# ProPrj_TweenWave_2025-11-29.net
KiCad netlist of a schematic drawn in EasyEDA Pro
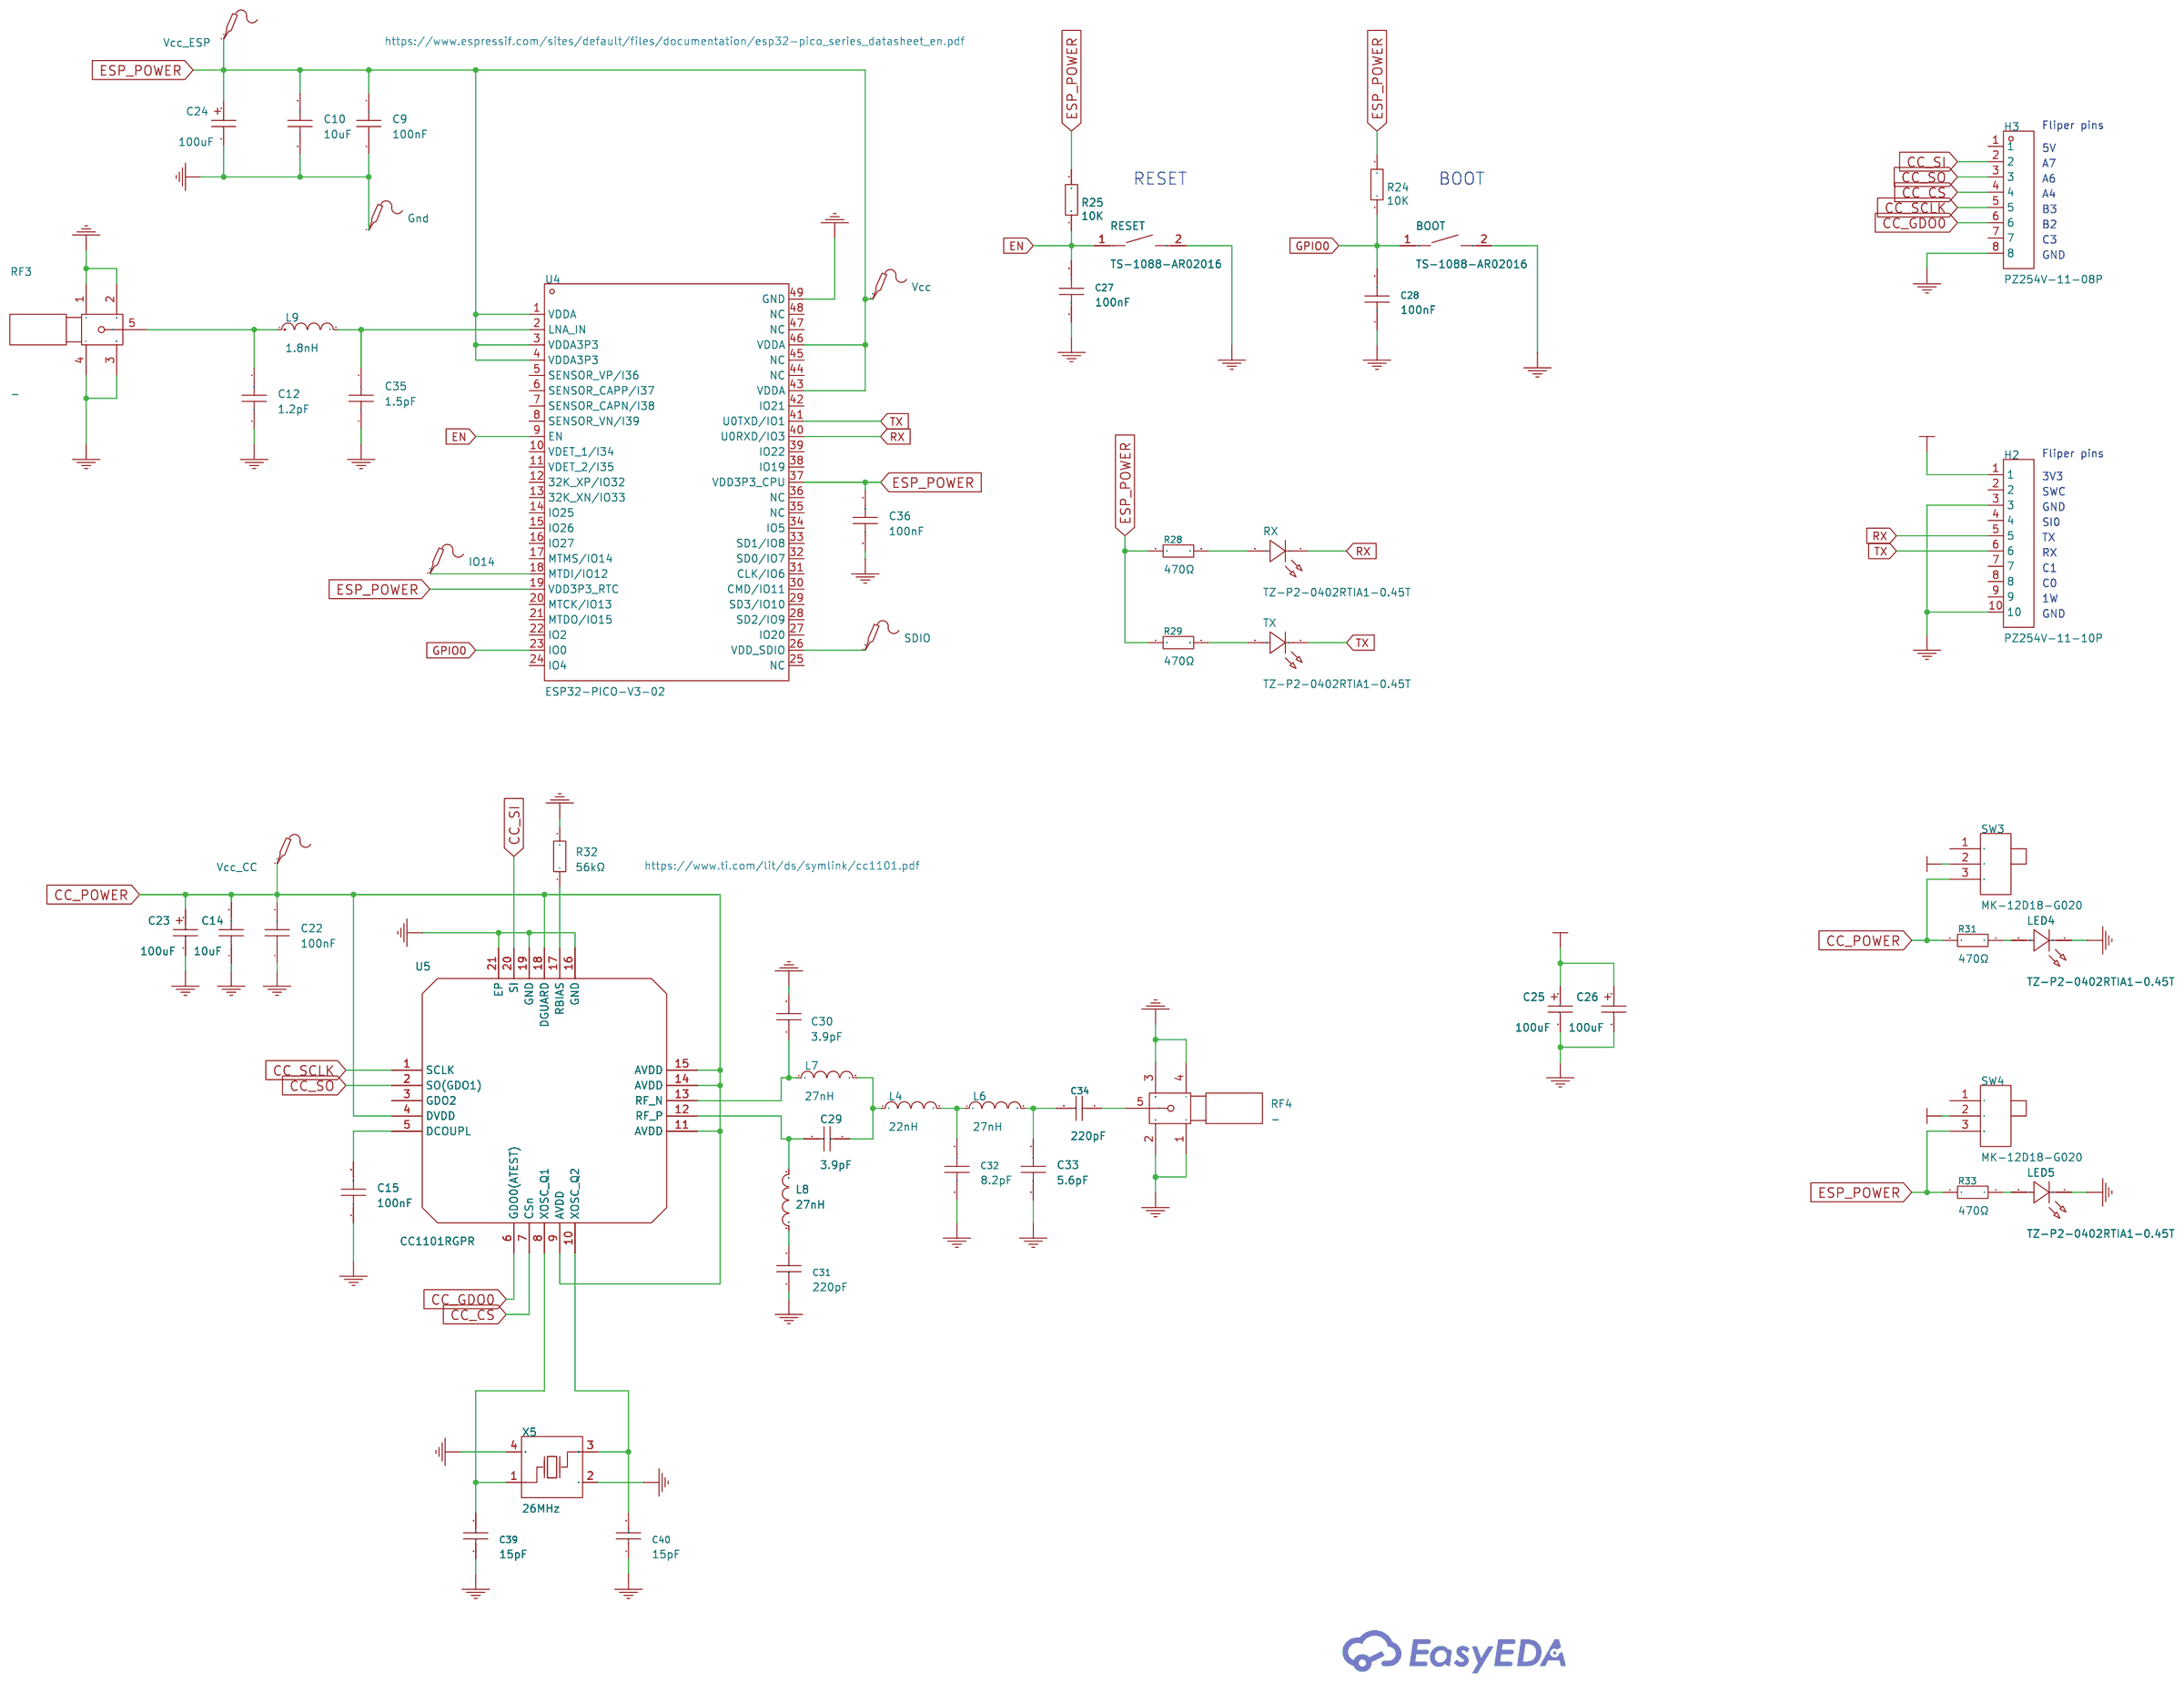
[diagram p0: schematic sheet]

(export (version "E")
  (design (tool "Eeschema 10.0.6"))
  (components
    (comp (ref "BOOT")
      (value "TS-1088-AR02016")
      (footprint "easyedapro:SW-SMD_L3.9-W3.0-P4.45")
      (fields (field (name "Manufacturer") "XUNPU(讯普)"))
      (libsource (lib "easyedapro") (part "TS-1088-AR02016"))
    )
    (comp (ref "C9")
      (value "100nF")
      (footprint "easyedapro:C0603")
      (description "Capacitance:100nF Tolerance:±10% Tolerance:±10% Voltage Rating:50V Temperature Coefficient:X7R")
      (fields
        (field (name "Manufacturer Part") "CC0603KRX7R9BB104")
        (field (name "Manufacturer") "YAGEO(国巨)")
      )
      (libsource (lib "easyedapro") (part "CC0603KRX7R9BB104"))
    )
    (comp (ref "C10")
      (value "10uF")
      (footprint "easyedapro:C0603")
      (fields
        (field (name "Manufacturer Part") "CL10A106MP8NNNC")
        (field (name "Manufacturer") "SAMSUNG(三星)")
      )
      (libsource (lib "easyedapro") (part "CL10A106MP8NNNC"))
    )
    (comp (ref "C12")
      (value "1.2pF")
      (footprint "easyedapro:C0201")
      (fields
        (field (name "Manufacturer Part") "GRM0335C1H1R2BA01D")
        (field (name "Manufacturer") "muRata(村田)")
      )
      (libsource (lib "easyedapro") (part "GRM0335C1H1R2BA01D"))
    )
    (comp (ref "C14")
      (value "10uF")
      (footprint "easyedapro:C0603")
      (fields
        (field (name "Manufacturer Part") "CL10A106MP8NNNC")
        (field (name "Manufacturer") "SAMSUNG(三星)")
      )
      (libsource (lib "easyedapro") (part "CL10A106MP8NNNC"))
    )
    (comp (ref "C15")
      (value "100nF")
      (footprint "easyedapro:C0603")
      (description "Capacitance:100nF Tolerance:±10% Tolerance:±10% Voltage Rating:50V Temperature Coefficient:X7R")
      (fields
        (field (name "Manufacturer Part") "CC0603KRX7R9BB104")
        (field (name "Manufacturer") "YAGEO(国巨)")
      )
      (libsource (lib "easyedapro") (part "CC0603KRX7R9BB104"))
    )
    (comp (ref "C22")
      (value "100nF")
      (footprint "easyedapro:C0603")
      (description "Capacitance:100nF Tolerance:±10% Tolerance:±10% Voltage Rating:50V Temperature Coefficient:X7R")
      (fields
        (field (name "Manufacturer Part") "CC0603KRX7R9BB104")
        (field (name "Manufacturer") "YAGEO(国巨)")
      )
      (libsource (lib "easyedapro") (part "CC0603KRX7R9BB104"))
    )
    (comp (ref "C23")
      (value "100uF")
      (footprint "easyedapro:CASE-B_3528")
      (fields (field (name "Manufacturer Part") "TAJB107K006RNJ") (field (name "Manufacturer") "Kyocera AVX"))
      (libsource (lib "easyedapro") (part "TAJB107K006RNJ"))
    )
    (comp (ref "C24")
      (value "100uF")
      (footprint "easyedapro:CASE-B_3528")
      (fields (field (name "Manufacturer Part") "TAJB107K006RNJ") (field (name "Manufacturer") "Kyocera AVX"))
      (libsource (lib "easyedapro") (part "TAJB107K006RNJ"))
    )
    (comp (ref "C25")
      (value "100uF")
      (footprint "easyedapro:CASE-B_3528")
      (fields (field (name "Manufacturer Part") "TAJB107K006RNJ") (field (name "Manufacturer") "Kyocera AVX"))
      (libsource (lib "easyedapro") (part "TAJB107K006RNJ"))
    )
    (comp (ref "C26")
      (value "100uF")
      (footprint "easyedapro:CASE-B_3528")
      (fields (field (name "Manufacturer Part") "TAJB107K006RNJ") (field (name "Manufacturer") "Kyocera AVX"))
      (libsource (lib "easyedapro") (part "TAJB107K006RNJ"))
    )
    (comp (ref "C27")
      (value "100nF")
      (footprint "easyedapro:C0402")
      (fields
        (field (name "Manufacturer Part") "CC0402KRX7R7BB104")
        (field (name "Manufacturer") "YAGEO(国巨)")
      )
      (libsource (lib "easyedapro") (part "CC0402KRX7R7BB104"))
    )
    (comp (ref "C28")
      (value "100nF")
      (footprint "easyedapro:C0402")
      (fields
        (field (name "Manufacturer Part") "CC0402KRX7R7BB104")
        (field (name "Manufacturer") "YAGEO(国巨)")
      )
      (libsource (lib "easyedapro") (part "CC0402KRX7R7BB104"))
    )
    (comp (ref "C29")
      (value "3.9pF")
      (footprint "easyedapro:C0402")
      (fields (field (name "Manufacturer Part") "0402CG3R9C500NT") (field (name "Manufacturer") "FH(风华)"))
      (libsource (lib "easyedapro") (part "0402CG3R9C500NT"))
    )
    (comp (ref "C30")
      (value "3.9pF")
      (footprint "easyedapro:C0402")
      (fields (field (name "Manufacturer Part") "0402CG3R9C500NT") (field (name "Manufacturer") "FH(风华)"))
      (libsource (lib "easyedapro") (part "0402CG3R9C500NT"))
    )
    (comp (ref "C31")
      (value "220pF")
      (footprint "easyedapro:C0402")
      (description "Capacitance:220pF Tolerance:±5% Tolerance:±5% Voltage Rating:50V Temperature Coefficient:NP0")
      (fields
        (field (name "Manufacturer Part") "CC0402JRNPO9BN221")
        (field (name "Manufacturer") "YAGEO(国巨)")
      )
      (libsource (lib "easyedapro") (part "CC0402JRNPO9BN221"))
    )
    (comp (ref "C32")
      (value "8.2pF")
      (footprint "easyedapro:C0402")
      (fields
        (field (name "Manufacturer Part") "CC0402BRNPO9BN8R2")
        (field (name "Manufacturer") "YAGEO(国巨)")
      )
      (libsource (lib "easyedapro") (part "CC0402BRNPO9BN8R2"))
    )
    (comp (ref "C33")
      (value "5.6pF")
      (footprint "easyedapro:C0402")
      (fields
        (field (name "Manufacturer Part") "CC0402BRNPO9BN5R6")
        (field (name "Manufacturer") "YAGEO(国巨)")
      )
      (libsource (lib "easyedapro") (part "CC0402BRNPO9BN5R6"))
    )
    (comp (ref "C34")
      (value "220pF")
      (footprint "easyedapro:C0402")
      (description "Capacitance:220pF Tolerance:±5% Tolerance:±5% Voltage Rating:50V Temperature Coefficient:NP0")
      (fields
        (field (name "Manufacturer Part") "CC0402JRNPO9BN221")
        (field (name "Manufacturer") "YAGEO(国巨)")
      )
      (libsource (lib "easyedapro") (part "CC0402JRNPO9BN221"))
    )
    (comp (ref "C35")
      (value "1.5pF")
      (footprint "easyedapro:C0201")
      (fields
        (field (name "Manufacturer Part") "GRM0335C1H1R5BA01D")
        (field (name "Manufacturer") "muRata(村田)")
      )
      (libsource (lib "easyedapro") (part "GRM0335C1H1R5BA01D"))
    )
    (comp (ref "C36")
      (value "100nF")
      (footprint "easyedapro:C0603")
      (description "Capacitance:100nF Tolerance:±10% Tolerance:±10% Voltage Rating:50V Temperature Coefficient:X7R")
      (fields
        (field (name "Manufacturer Part") "CC0603KRX7R9BB104")
        (field (name "Manufacturer") "YAGEO(国巨)")
      )
      (libsource (lib "easyedapro") (part "CC0603KRX7R9BB104"))
    )
    (comp (ref "C39")
      (value "15pF")
      (footprint "easyedapro:C0402")
      (fields
        (field (name "Manufacturer Part") "CC0402JRNPO9BN150")
        (field (name "Manufacturer") "YAGEO(国巨)")
      )
      (libsource (lib "easyedapro") (part "CC0402JRNPO9BN150"))
    )
    (comp (ref "C40")
      (value "15pF")
      (footprint "easyedapro:C0402")
      (fields
        (field (name "Manufacturer Part") "CC0402JRNPO9BN150")
        (field (name "Manufacturer") "YAGEO(国巨)")
      )
      (libsource (lib "easyedapro") (part "CC0402JRNPO9BN150"))
    )
    (comp (ref "Gnd")
      (value "~")
      (footprint "easyedapro:Test-Point-0.5mm")
      (description "Test Point 测试点")
      (libsource (lib "easyedapro") (part "Test-Point"))
    )
    (comp (ref "H2")
      (value "PZ254V-11-10P")
      (footprint "easyedapro:HDR-TH_10P-P2.54-V-M")
      (fields (field (name "Manufacturer") "XFCN(兴飞)"))
      (libsource (lib "easyedapro") (part "PZ254V-11-10P"))
    )
    (comp (ref "H3")
      (value "PZ254V-11-08P")
      (footprint "easyedapro:HDR-TH_8P-P2.54-V-M")
      (fields (field (name "Manufacturer") "XFCN(兴飞)"))
      (libsource (lib "easyedapro") (part "PZ254V-11-08P"))
    )
    (comp (ref "IO14")
      (value "~")
      (footprint "easyedapro:Test-Point-0.5mm")
      (description "Test Point 测试点")
      (libsource (lib "easyedapro") (part "Test-Point"))
    )
    (comp (ref "L4")
      (value "22nH")
      (footprint "easyedapro:L0402")
      (fields (field (name "Manufacturer Part") "LQG15HS22NJ02D") (field (name "Manufacturer") "muRata(村田)"))
      (libsource (lib "easyedapro") (part "LQG15HS22NJ02D"))
    )
    (comp (ref "L6")
      (value "27nH")
      (footprint "easyedapro:L0402-RD")
      (fields (field (name "Manufacturer Part") "LQG15HS27NJ02D") (field (name "Manufacturer") "muRata(村田)"))
      (libsource (lib "easyedapro") (part "LQG15HS27NJ02D"))
    )
    (comp (ref "L7")
      (value "27nH")
      (footprint "easyedapro:L0402-RD")
      (fields (field (name "Manufacturer Part") "LQG15HS27NJ02D") (field (name "Manufacturer") "muRata(村田)"))
      (libsource (lib "easyedapro") (part "LQG15HS27NJ02D"))
    )
    (comp (ref "L8")
      (value "27nH")
      (footprint "easyedapro:L0402-RD")
      (fields (field (name "Manufacturer Part") "LQG15HS27NJ02D") (field (name "Manufacturer") "muRata(村田)"))
      (libsource (lib "easyedapro") (part "LQG15HS27NJ02D"))
    )
    (comp (ref "L9")
      (value "1.8nH")
      (footprint "easyedapro:L0201-RD")
      (fields (field (name "Manufacturer Part") "LQP03TN1N8B02D") (field (name "Manufacturer") "muRata(村田)"))
      (libsource (lib "easyedapro") (part "LQP03TN1N8B02D"))
    )
    (comp (ref "LED4")
      (value "TZ-P2-0402RTIA1-0.45T")
      (footprint "easyedapro:LED0402-RD_RED")
      (fields (field (name "Manufacturer") "TUOZHAN(拓展光电)"))
      (libsource (lib "easyedapro") (part "TZ-P2-0402RTIA1-0.45T"))
    )
    (comp (ref "LED5")
      (value "TZ-P2-0402RTIA1-0.45T")
      (footprint "easyedapro:LED0402-RD_RED")
      (fields (field (name "Manufacturer") "TUOZHAN(拓展光电)"))
      (libsource (lib "easyedapro") (part "TZ-P2-0402RTIA1-0.45T"))
    )
    (comp (ref "R24")
      (value "10K")
      (footprint "easyedapro:R0603")
      (fields (field (name "Manufacturer Part") "RC0603DR-0710KL") (field (name "Manufacturer") "YAGEO(国巨)"))
      (libsource (lib "easyedapro") (part "10K"))
    )
    (comp (ref "R25")
      (value "10K")
      (footprint "easyedapro:R0603")
      (fields (field (name "Manufacturer Part") "RC0603DR-0710KL") (field (name "Manufacturer") "YAGEO(国巨)"))
      (libsource (lib "easyedapro") (part "10K"))
    )
    (comp (ref "R28")
      (value "470Ω")
      (footprint "easyedapro:R0402")
      (fields
        (field (name "Manufacturer Part") "0402WGF4700TCE")
        (field (name "Manufacturer") "UNI-ROYAL(厚声)")
      )
      (libsource (lib "easyedapro") (part "0402WGF4700TCE"))
    )
    (comp (ref "R29")
      (value "470Ω")
      (footprint "easyedapro:R0402")
      (fields
        (field (name "Manufacturer Part") "0402WGF4700TCE")
        (field (name "Manufacturer") "UNI-ROYAL(厚声)")
      )
      (libsource (lib "easyedapro") (part "0402WGF4700TCE"))
    )
    (comp (ref "R31")
      (value "470Ω")
      (footprint "easyedapro:R0402")
      (fields
        (field (name "Manufacturer Part") "0402WGF4700TCE")
        (field (name "Manufacturer") "UNI-ROYAL(厚声)")
      )
      (libsource (lib "easyedapro") (part "0402WGF4700TCE"))
    )
    (comp (ref "R32")
      (value "56kΩ")
      (footprint "easyedapro:R0402")
      (fields
        (field (name "Manufacturer Part") "0402WGF5602TCE")
        (field (name "Manufacturer") "UNI-ROYAL(厚声)")
      )
      (libsource (lib "easyedapro") (part "0402WGF5602TCE"))
    )
    (comp (ref "R33")
      (value "470Ω")
      (footprint "easyedapro:R0402")
      (fields
        (field (name "Manufacturer Part") "0402WGF4700TCE")
        (field (name "Manufacturer") "UNI-ROYAL(厚声)")
      )
      (libsource (lib "easyedapro") (part "0402WGF4700TCE"))
    )
    (comp (ref "RESET")
      (value "TS-1088-AR02016")
      (footprint "easyedapro:SW-SMD_L3.9-W3.0-P4.45")
      (fields (field (name "Manufacturer") "XUNPU(讯普)"))
      (libsource (lib "easyedapro") (part "TS-1088-AR02016"))
    )
    (comp (ref "RF3")
      (value "-")
      (footprint "easyedapro:SMA-SMD_BWSMA-KE-P001")
      (fields
        (field (name "Manufacturer Part") "BWSMA-KE-P001")
        (field (name "Manufacturer") "BAT WIRELESS(蝙蝠无线)")
      )
      (libsource (lib "easyedapro") (part "BWSMA-KE-P001"))
    )
    (comp (ref "RF4")
      (value "-")
      (footprint "easyedapro:SMA-SMD_BWSMA-KE-P001")
      (fields
        (field (name "Manufacturer Part") "BWSMA-KE-P001")
        (field (name "Manufacturer") "BAT WIRELESS(蝙蝠无线)")
      )
      (libsource (lib "easyedapro") (part "BWSMA-KE-P001"))
    )
    (comp (ref "RX")
      (value "TZ-P2-0402RTIA1-0.45T")
      (footprint "easyedapro:LED0402-RD_RED")
      (fields (field (name "Manufacturer") "TUOZHAN(拓展光电)"))
      (libsource (lib "easyedapro") (part "TZ-P2-0402RTIA1-0.45T"))
    )
    (comp (ref "SDIO")
      (value "~")
      (footprint "easyedapro:Test-Point-0.5mm")
      (description "Test Point 测试点")
      (libsource (lib "easyedapro") (part "Test-Point"))
    )
    (comp (ref "SW3")
      (value "MK-12D18-G020")
      (footprint "easyedapro:SW-TH_MK-12D18-G040")
      (fields (field (name "Manufacturer") "G-Switch(品赞)"))
      (libsource (lib "easyedapro") (part "MK-12D18-G020"))
    )
    (comp (ref "SW4")
      (value "MK-12D18-G020")
      (footprint "easyedapro:SW-TH_MK-12D18-G040")
      (fields (field (name "Manufacturer") "G-Switch(品赞)"))
      (libsource (lib "easyedapro") (part "MK-12D18-G020"))
    )
    (comp (ref "TX")
      (value "TZ-P2-0402RTIA1-0.45T")
      (footprint "easyedapro:LED0402-RD_RED")
      (fields (field (name "Manufacturer") "TUOZHAN(拓展光电)"))
      (libsource (lib "easyedapro") (part "TZ-P2-0402RTIA1-0.45T"))
    )
    (comp (ref "U4")
      (value "ESP32-PICO-V3-02")
      (footprint "easyedapro:QFN-48_L7.0-W7.0-P0.50-BL-EP5.1")
      (fields (field (name "Manufacturer") "ESPRESSIF(乐鑫)"))
      (libsource (lib "easyedapro") (part "ESP32-PICO-V3-02"))
    )
    (comp (ref "U5")
      (value "CC1101RGPR")
      (footprint "easyedapro:QFN-20_L4.0-W4.0-P0.5-TL-EP")
      (fields (field (name "Manufacturer") "TI(德州仪器)"))
      (libsource (lib "easyedapro") (part "CC1101RGPR"))
    )
    (comp (ref "Vcc")
      (value "~")
      (footprint "easyedapro:Test-Point-0.5mm")
      (description "Test Point 测试点")
      (libsource (lib "easyedapro") (part "Test-Point"))
    )
    (comp (ref "Vcc_CC")
      (value "~")
      (footprint "easyedapro:Test-Point-0.5mm")
      (description "Test Point 测试点")
      (libsource (lib "easyedapro") (part "Test-Point"))
    )
    (comp (ref "Vcc_ESP")
      (value "~")
      (footprint "easyedapro:Test-Point-0.5mm")
      (description "Test Point 测试点")
      (libsource (lib "easyedapro") (part "Test-Point"))
    )
    (comp (ref "X5")
      (value "26MHz")
      (footprint "easyedapro:CRYSTAL-SMD_4P-L3.2-W2.5-BL")
      (fields (field (name "Manufacturer Part") "X322526MMB4SI") (field (name "Manufacturer") "YXC(扬兴晶振)"))
      (libsource (lib "easyedapro") (part "X322526MMB4SI"))
    )
  )
  (nets
    (net (code "1") (name "3V3") (class "Default")
      (node (ref "C25") (pin "1") (pinfunction "1_1") (pintype "input"))
      (node (ref "C26") (pin "1") (pinfunction "1_1") (pintype "input"))
      (node (ref "H2") (pin "1") (pinfunction "1_1") (pintype "unspecified"))
      (node (ref "SW3") (pin "2") (pinfunction "2_2") (pintype "unspecified"))
      (node (ref "SW4") (pin "2") (pinfunction "2_2") (pintype "unspecified"))
    )
    (net (code "2") (name "CC_CS") (class "Default")
      (node (ref "H3") (pin "4") (pinfunction "4_4") (pintype "unspecified"))
      (node (ref "U5") (pin "7") (pinfunction "CSn_7") (pintype "unspecified"))
    )
    (net (code "3") (name "CC_GDO0") (class "Default")
      (node (ref "H3") (pin "6") (pinfunction "6_6") (pintype "unspecified"))
      (node (ref "U5") (pin "6") (pinfunction "GDO0(ATEST)_6") (pintype "unspecified"))
    )
    (net (code "4") (name "CC_POWER") (class "Default")
      (node (ref "C14") (pin "2") (pinfunction "2_2") (pintype "unspecified"))
      (node (ref "C22") (pin "2") (pinfunction "2_2") (pintype "unspecified"))
      (node (ref "C23") (pin "1") (pinfunction "1_1") (pintype "input"))
      (node (ref "R31") (pin "1") (pinfunction "1_1") (pintype "input"))
      (node (ref "SW3") (pin "3") (pinfunction "3_3") (pintype "unspecified"))
      (node (ref "U5") (pin "11") (pinfunction "AVDD_11") (pintype "unspecified"))
      (node (ref "U5") (pin "14") (pinfunction "AVDD_14") (pintype "unspecified"))
      (node (ref "U5") (pin "15") (pinfunction "AVDD_15") (pintype "unspecified"))
      (node (ref "U5") (pin "18") (pinfunction "DGUARD_18") (pintype "unspecified"))
      (node (ref "U5") (pin "4") (pinfunction "DVDD_4") (pintype "unspecified"))
      (node (ref "U5") (pin "9") (pinfunction "AVDD_9") (pintype "unspecified"))
      (node (ref "Vcc_CC") (pin "1") (pinfunction "1_1") (pintype "unspecified"))
    )
    (net (code "5") (name "CC_SCLK") (class "Default")
      (node (ref "H3") (pin "5") (pinfunction "5_5") (pintype "unspecified"))
      (node (ref "U5") (pin "1") (pinfunction "SCLK_1") (pintype "unspecified"))
    )
    (net (code "6") (name "CC_SI") (class "Default")
      (node (ref "H3") (pin "2") (pinfunction "2_2") (pintype "unspecified"))
      (node (ref "U5") (pin "20") (pinfunction "SI_20") (pintype "unspecified"))
    )
    (net (code "7") (name "CC_SO") (class "Default")
      (node (ref "H3") (pin "3") (pinfunction "3_3") (pintype "unspecified"))
      (node (ref "U5") (pin "2") (pinfunction "SO(GDO1)_2") (pintype "unspecified"))
    )
    (net (code "8") (name "EN") (class "Default")
      (node (ref "C27") (pin "2") (pinfunction "2_2") (pintype "input"))
      (node (ref "R25") (pin "1") (pinfunction "1_1") (pintype "input"))
      (node (ref "RESET") (pin "1") (pinfunction "1_1") (pintype "unspecified"))
      (node (ref "U4") (pin "9") (pinfunction "EN_9") (pintype "unspecified"))
    )
    (net (code "9") (name "ESP_POWER") (class "Default")
      (node (ref "C10") (pin "2") (pinfunction "2_2") (pintype "unspecified"))
      (node (ref "C24") (pin "1") (pinfunction "1_1") (pintype "input"))
      (node (ref "C36") (pin "2") (pinfunction "2_2") (pintype "unspecified"))
      (node (ref "C9") (pin "2") (pinfunction "2_2") (pintype "unspecified"))
      (node (ref "R24") (pin "2") (pinfunction "2_2") (pintype "input"))
      (node (ref "R25") (pin "2") (pinfunction "2_2") (pintype "input"))
      (node (ref "R28") (pin "1") (pinfunction "1_1") (pintype "input"))
      (node (ref "R29") (pin "1") (pinfunction "1_1") (pintype "input"))
      (node (ref "R33") (pin "1") (pinfunction "1_1") (pintype "input"))
      (node (ref "SW4") (pin "3") (pinfunction "3_3") (pintype "unspecified"))
      (node (ref "U4") (pin "1") (pinfunction "VDDA_1") (pintype "unspecified"))
      (node (ref "U4") (pin "19") (pinfunction "VDD3P3_RTC_19") (pintype "unspecified"))
      (node (ref "U4") (pin "3") (pinfunction "VDDA3P3_3") (pintype "unspecified"))
      (node (ref "U4") (pin "37") (pinfunction "VDD3P3_CPU_37") (pintype "unspecified"))
      (node (ref "U4") (pin "4") (pinfunction "VDDA3P3_4") (pintype "unspecified"))
      (node (ref "U4") (pin "43") (pinfunction "VDDA_43") (pintype "unspecified"))
      (node (ref "U4") (pin "46") (pinfunction "VDDA_46") (pintype "unspecified"))
      (node (ref "Vcc") (pin "1") (pinfunction "1_1") (pintype "unspecified"))
      (node (ref "Vcc_ESP") (pin "1") (pinfunction "1_1") (pintype "unspecified"))
    )
    (net (code "10") (name "GND") (class "Default")
      (node (ref "BOOT") (pin "2") (pinfunction "2_2") (pintype "unspecified"))
      (node (ref "C10") (pin "1") (pinfunction "1_1") (pintype "unspecified"))
      (node (ref "C12") (pin "1") (pinfunction "1_1") (pintype "unspecified"))
      (node (ref "C14") (pin "1") (pinfunction "1_1") (pintype "unspecified"))
      (node (ref "C15") (pin "1") (pinfunction "1_1") (pintype "unspecified"))
      (node (ref "C22") (pin "1") (pinfunction "1_1") (pintype "unspecified"))
      (node (ref "C23") (pin "2") (pinfunction "2_2") (pintype "input"))
      (node (ref "C24") (pin "2") (pinfunction "2_2") (pintype "input"))
      (node (ref "C25") (pin "2") (pinfunction "2_2") (pintype "input"))
      (node (ref "C26") (pin "2") (pinfunction "2_2") (pintype "input"))
      (node (ref "C27") (pin "1") (pinfunction "1_1") (pintype "input"))
      (node (ref "C28") (pin "1") (pinfunction "1_1") (pintype "input"))
      (node (ref "C30") (pin "2") (pinfunction "2_2") (pintype "input"))
      (node (ref "C31") (pin "1") (pinfunction "1_1") (pintype "input"))
      (node (ref "C32") (pin "2") (pinfunction "2_2") (pintype "input"))
      (node (ref "C33") (pin "1") (pinfunction "1_1") (pintype "unspecified"))
      (node (ref "C35") (pin "1") (pinfunction "1_1") (pintype "unspecified"))
      (node (ref "C36") (pin "1") (pinfunction "1_1") (pintype "unspecified"))
      (node (ref "C39") (pin "1") (pinfunction "1_1") (pintype "input"))
      (node (ref "C40") (pin "1") (pinfunction "1_1") (pintype "input"))
      (node (ref "C9") (pin "1") (pinfunction "1_1") (pintype "unspecified"))
      (node (ref "Gnd") (pin "1") (pinfunction "1_1") (pintype "unspecified"))
      (node (ref "H2") (pin "10") (pinfunction "10_10") (pintype "unspecified"))
      (node (ref "H2") (pin "3") (pinfunction "3_3") (pintype "unspecified"))
      (node (ref "H3") (pin "8") (pinfunction "8_8") (pintype "unspecified"))
      (node (ref "LED4") (pin "1") (pinfunction "K_1") (pintype "unspecified"))
      (node (ref "LED5") (pin "1") (pinfunction "K_1") (pintype "unspecified"))
      (node (ref "R32") (pin "2") (pinfunction "2_2") (pintype "input"))
      (node (ref "RESET") (pin "2") (pinfunction "2_2") (pintype "unspecified"))
      (node (ref "RF3") (pin "1") (pinfunction "1_1") (pintype "unspecified"))
      (node (ref "RF3") (pin "2") (pinfunction "2_2") (pintype "unspecified"))
      (node (ref "RF3") (pin "3") (pinfunction "3_3") (pintype "unspecified"))
      (node (ref "RF3") (pin "4") (pinfunction "4_4") (pintype "unspecified"))
      (node (ref "RF4") (pin "1") (pinfunction "1_1") (pintype "unspecified"))
      (node (ref "RF4") (pin "2") (pinfunction "2_2") (pintype "unspecified"))
      (node (ref "RF4") (pin "3") (pinfunction "3_3") (pintype "unspecified"))
      (node (ref "RF4") (pin "4") (pinfunction "4_4") (pintype "unspecified"))
      (node (ref "U4") (pin "49") (pinfunction "GND_49") (pintype "unspecified"))
      (node (ref "U5") (pin "16") (pinfunction "GND_16") (pintype "unspecified"))
      (node (ref "U5") (pin "19") (pinfunction "GND_19") (pintype "unspecified"))
      (node (ref "U5") (pin "21") (pinfunction "EP_21") (pintype "unspecified"))
      (node (ref "X5") (pin "2") (pinfunction "GND_2") (pintype "unspecified"))
      (node (ref "X5") (pin "4") (pinfunction "GND_4") (pintype "unspecified"))
    )
    (net (code "11") (name "GPIO0") (class "Default")
      (node (ref "BOOT") (pin "1") (pinfunction "1_1") (pintype "unspecified"))
      (node (ref "C28") (pin "2") (pinfunction "2_2") (pintype "input"))
      (node (ref "R24") (pin "1") (pinfunction "1_1") (pintype "input"))
      (node (ref "U4") (pin "23") (pinfunction "IO0_23") (pintype "unspecified"))
    )
    (net (code "12") (name "Net-(C12-Pad2)") (class "Default")
      (node (ref "C12") (pin "2") (pinfunction "2_2") (pintype "unspecified"))
      (node (ref "L9") (pin "1") (pinfunction "1_1") (pintype "input"))
      (node (ref "RF3") (pin "5") (pinfunction "5_5") (pintype "unspecified"))
    )
    (net (code "13") (name "Net-(C29-Pad2)") (class "Default")
      (node (ref "C29") (pin "2") (pinfunction "2_2") (pintype "input"))
      (node (ref "L4") (pin "1") (pinfunction "1_1") (pintype "unspecified"))
      (node (ref "L7") (pin "2") (pinfunction "2_2") (pintype "unspecified"))
    )
    (net (code "14") (name "Net-(C31-Pad2)") (class "Default")
      (node (ref "C31") (pin "2") (pinfunction "2_2") (pintype "input"))
      (node (ref "L8") (pin "1") (pinfunction "1_1") (pintype "unspecified"))
    )
    (net (code "15") (name "Net-(C32-Pad1)") (class "Default")
      (node (ref "C32") (pin "1") (pinfunction "1_1") (pintype "input"))
      (node (ref "L4") (pin "2") (pinfunction "2_2") (pintype "unspecified"))
      (node (ref "L6") (pin "1") (pinfunction "1_1") (pintype "unspecified"))
    )
    (net (code "16") (name "Net-(C33-Pad2)") (class "Default")
      (node (ref "C33") (pin "2") (pinfunction "2_2") (pintype "unspecified"))
      (node (ref "C34") (pin "2") (pinfunction "2_2") (pintype "input"))
      (node (ref "L6") (pin "2") (pinfunction "2_2") (pintype "unspecified"))
    )
    (net (code "17") (name "Net-(C34-Pad1)") (class "Default")
      (node (ref "C34") (pin "1") (pinfunction "1_1") (pintype "input"))
      (node (ref "RF4") (pin "5") (pinfunction "5_5") (pintype "unspecified"))
    )
    (net (code "18") (name "Net-(LED4-A)") (class "Default")
      (node (ref "LED4") (pin "2") (pinfunction "A_2") (pintype "unspecified"))
      (node (ref "R31") (pin "2") (pinfunction "2_2") (pintype "input"))
    )
    (net (code "19") (name "Net-(LED5-A)") (class "Default")
      (node (ref "LED5") (pin "2") (pinfunction "A_2") (pintype "unspecified"))
      (node (ref "R33") (pin "2") (pinfunction "2_2") (pintype "input"))
    )
    (net (code "20") (name "Net-(RX-A)") (class "Default")
      (node (ref "R28") (pin "2") (pinfunction "2_2") (pintype "input"))
      (node (ref "RX") (pin "2") (pinfunction "A_2") (pintype "unspecified"))
    )
    (net (code "21") (name "Net-(TX-A)") (class "Default")
      (node (ref "R29") (pin "2") (pinfunction "2_2") (pintype "input"))
      (node (ref "TX") (pin "2") (pinfunction "A_2") (pintype "unspecified"))
    )
    (net (code "22") (name "Net-(U4-LNA_IN)") (class "Default")
      (node (ref "C35") (pin "2") (pinfunction "2_2") (pintype "unspecified"))
      (node (ref "L9") (pin "2") (pinfunction "2_2") (pintype "input"))
      (node (ref "U4") (pin "2") (pinfunction "LNA_IN_2") (pintype "unspecified"))
    )
    (net (code "23") (name "Net-(U4-MTDI{slash}IO12)") (class "Default")
      (node (ref "IO14") (pin "1") (pinfunction "1_1") (pintype "unspecified"))
      (node (ref "U4") (pin "18") (pinfunction "MTDI/IO12_18") (pintype "unspecified"))
    )
    (net (code "24") (name "Net-(U4-VDD_SDIO)") (class "Default")
      (node (ref "SDIO") (pin "1") (pinfunction "1_1") (pintype "unspecified"))
      (node (ref "U4") (pin "26") (pinfunction "VDD_SDIO_26") (pintype "unspecified"))
    )
    (net (code "25") (name "Net-(U5-DCOUPL)") (class "Default")
      (node (ref "C15") (pin "2") (pinfunction "2_2") (pintype "unspecified"))
      (node (ref "U5") (pin "5") (pinfunction "DCOUPL_5") (pintype "unspecified"))
    )
    (net (code "26") (name "Net-(U5-RBIAS)") (class "Default")
      (node (ref "R32") (pin "1") (pinfunction "1_1") (pintype "input"))
      (node (ref "U5") (pin "17") (pinfunction "RBIAS_17") (pintype "unspecified"))
    )
    (net (code "27") (name "Net-(U5-RF_N)") (class "Default")
      (node (ref "C30") (pin "1") (pinfunction "1_1") (pintype "input"))
      (node (ref "L7") (pin "1") (pinfunction "1_1") (pintype "unspecified"))
      (node (ref "U5") (pin "13") (pinfunction "RF_N_13") (pintype "unspecified"))
    )
    (net (code "28") (name "Net-(U5-RF_P)") (class "Default")
      (node (ref "C29") (pin "1") (pinfunction "1_1") (pintype "input"))
      (node (ref "L8") (pin "2") (pinfunction "2_2") (pintype "unspecified"))
      (node (ref "U5") (pin "12") (pinfunction "RF_P_12") (pintype "unspecified"))
    )
    (net (code "29") (name "Net-(U5-XOSC_Q1)") (class "Default")
      (node (ref "C39") (pin "2") (pinfunction "2_2") (pintype "input"))
      (node (ref "U5") (pin "8") (pinfunction "XOSC_Q1_8") (pintype "unspecified"))
      (node (ref "X5") (pin "1") (pinfunction "OSC1_1") (pintype "unspecified"))
    )
    (net (code "30") (name "Net-(U5-XOSC_Q2)") (class "Default")
      (node (ref "C40") (pin "2") (pinfunction "2_2") (pintype "input"))
      (node (ref "U5") (pin "10") (pinfunction "XOSC_Q2_10") (pintype "unspecified"))
      (node (ref "X5") (pin "3") (pinfunction "OSC2_3") (pintype "unspecified"))
    )
    (net (code "31") (name "RX") (class "Default")
      (node (ref "H2") (pin "5") (pinfunction "5_5") (pintype "unspecified"))
      (node (ref "RX") (pin "1") (pinfunction "K_1") (pintype "unspecified"))
      (node (ref "U4") (pin "40") (pinfunction "U0RXD/IO3_40") (pintype "unspecified"))
    )
    (net (code "32") (name "TX") (class "Default")
      (node (ref "H2") (pin "6") (pinfunction "6_6") (pintype "unspecified"))
      (node (ref "TX") (pin "1") (pinfunction "K_1") (pintype "unspecified"))
      (node (ref "U4") (pin "41") (pinfunction "U0TXD/IO1_41") (pintype "unspecified"))
    )
    (net (code "33") (name "unconnected-(H2-Pad2)") (class "Default")
      (node (ref "H2") (pin "2") (pinfunction "2_2") (pintype "unspecified"))
    )
    (net (code "34") (name "unconnected-(H2-Pad4)") (class "Default")
      (node (ref "H2") (pin "4") (pinfunction "4_4") (pintype "unspecified"))
    )
    (net (code "35") (name "unconnected-(H2-Pad7)") (class "Default")
      (node (ref "H2") (pin "7") (pinfunction "7_7") (pintype "unspecified"))
    )
    (net (code "36") (name "unconnected-(H2-Pad8)") (class "Default")
      (node (ref "H2") (pin "8") (pinfunction "8_8") (pintype "unspecified"))
    )
    (net (code "37") (name "unconnected-(H2-Pad9)") (class "Default")
      (node (ref "H2") (pin "9") (pinfunction "9_9") (pintype "unspecified"))
    )
    (net (code "38") (name "unconnected-(H3-Pad1)") (class "Default")
      (node (ref "H3") (pin "1") (pinfunction "1_1") (pintype "unspecified"))
    )
    (net (code "39") (name "unconnected-(H3-Pad7)") (class "Default")
      (node (ref "H3") (pin "7") (pinfunction "7_7") (pintype "unspecified"))
    )
    (net (code "40") (name "unconnected-(SW3-Pad1)") (class "Default")
      (node (ref "SW3") (pin "1") (pinfunction "1_1") (pintype "unspecified"))
    )
    (net (code "41") (name "unconnected-(SW4-Pad1)") (class "Default")
      (node (ref "SW4") (pin "1") (pinfunction "1_1") (pintype "unspecified"))
    )
    (net (code "42") (name "unconnected-(U4-32K_XN{slash}IO33-Pad13)") (class "Default")
      (node (ref "U4") (pin "13") (pinfunction "32K_XN/IO33_13") (pintype "unspecified"))
    )
    (net (code "43") (name "unconnected-(U4-32K_XP{slash}IO32-Pad12)") (class "Default")
      (node (ref "U4") (pin "12") (pinfunction "32K_XP/IO32_12") (pintype "unspecified"))
    )
    (net (code "44") (name "unconnected-(U4-CLK{slash}IO6-Pad31)") (class "Default")
      (node (ref "U4") (pin "31") (pinfunction "CLK/IO6_31") (pintype "unspecified"))
    )
    (net (code "45") (name "unconnected-(U4-CMD{slash}IO11-Pad30)") (class "Default")
      (node (ref "U4") (pin "30") (pinfunction "CMD/IO11_30") (pintype "unspecified"))
    )
    (net (code "46") (name "unconnected-(U4-IO2-Pad22)") (class "Default")
      (node (ref "U4") (pin "22") (pinfunction "IO2_22") (pintype "unspecified"))
    )
    (net (code "47") (name "unconnected-(U4-IO4-Pad24)") (class "Default")
      (node (ref "U4") (pin "24") (pinfunction "IO4_24") (pintype "unspecified"))
    )
    (net (code "48") (name "unconnected-(U4-IO5-Pad34)") (class "Default")
      (node (ref "U4") (pin "34") (pinfunction "IO5_34") (pintype "unspecified"))
    )
    (net (code "49") (name "unconnected-(U4-IO19-Pad38)") (class "Default")
      (node (ref "U4") (pin "38") (pinfunction "IO19_38") (pintype "unspecified"))
    )
    (net (code "50") (name "unconnected-(U4-IO20-Pad27)") (class "Default")
      (node (ref "U4") (pin "27") (pinfunction "IO20_27") (pintype "unspecified"))
    )
    (net (code "51") (name "unconnected-(U4-IO21-Pad42)") (class "Default")
      (node (ref "U4") (pin "42") (pinfunction "IO21_42") (pintype "unspecified"))
    )
    (net (code "52") (name "unconnected-(U4-IO22-Pad39)") (class "Default")
      (node (ref "U4") (pin "39") (pinfunction "IO22_39") (pintype "unspecified"))
    )
    (net (code "53") (name "unconnected-(U4-IO25-Pad14)") (class "Default")
      (node (ref "U4") (pin "14") (pinfunction "IO25_14") (pintype "unspecified"))
    )
    (net (code "54") (name "unconnected-(U4-IO26-Pad15)") (class "Default")
      (node (ref "U4") (pin "15") (pinfunction "IO26_15") (pintype "unspecified"))
    )
    (net (code "55") (name "unconnected-(U4-IO27-Pad16)") (class "Default")
      (node (ref "U4") (pin "16") (pinfunction "IO27_16") (pintype "unspecified"))
    )
    (net (code "56") (name "unconnected-(U4-MTCK{slash}IO13-Pad20)") (class "Default")
      (node (ref "U4") (pin "20") (pinfunction "MTCK/IO13_20") (pintype "unspecified"))
    )
    (net (code "57") (name "unconnected-(U4-MTDO{slash}IO15-Pad21)") (class "Default")
      (node (ref "U4") (pin "21") (pinfunction "MTDO/IO15_21") (pintype "unspecified"))
    )
    (net (code "58") (name "unconnected-(U4-MTMS{slash}IO14-Pad17)") (class "Default")
      (node (ref "U4") (pin "17") (pinfunction "MTMS/IO14_17") (pintype "unspecified"))
    )
    (net (code "59") (name "unconnected-(U4-NC-Pad25)") (class "Default")
      (node (ref "U4") (pin "25") (pinfunction "NC_25") (pintype "unspecified"))
    )
    (net (code "60") (name "unconnected-(U4-NC-Pad35)") (class "Default")
      (node (ref "U4") (pin "35") (pinfunction "NC_35") (pintype "unspecified"))
    )
    (net (code "61") (name "unconnected-(U4-NC-Pad36)") (class "Default")
      (node (ref "U4") (pin "36") (pinfunction "NC_36") (pintype "unspecified"))
    )
    (net (code "62") (name "unconnected-(U4-NC-Pad44)") (class "Default")
      (node (ref "U4") (pin "44") (pinfunction "NC_44") (pintype "unspecified"))
    )
    (net (code "63") (name "unconnected-(U4-NC-Pad45)") (class "Default")
      (node (ref "U4") (pin "45") (pinfunction "NC_45") (pintype "unspecified"))
    )
    (net (code "64") (name "unconnected-(U4-NC-Pad47)") (class "Default")
      (node (ref "U4") (pin "47") (pinfunction "NC_47") (pintype "unspecified"))
    )
    (net (code "65") (name "unconnected-(U4-NC-Pad48)") (class "Default")
      (node (ref "U4") (pin "48") (pinfunction "NC_48") (pintype "unspecified"))
    )
    (net (code "66") (name "unconnected-(U4-SD0{slash}IO7-Pad32)") (class "Default")
      (node (ref "U4") (pin "32") (pinfunction "SD0/IO7_32") (pintype "unspecified"))
    )
    (net (code "67") (name "unconnected-(U4-SD1{slash}IO8-Pad33)") (class "Default")
      (node (ref "U4") (pin "33") (pinfunction "SD1/IO8_33") (pintype "unspecified"))
    )
    (net (code "68") (name "unconnected-(U4-SD2{slash}IO9-Pad28)") (class "Default")
      (node (ref "U4") (pin "28") (pinfunction "SD2/IO9_28") (pintype "unspecified"))
    )
    (net (code "69") (name "unconnected-(U4-SD3{slash}IO10-Pad29)") (class "Default")
      (node (ref "U4") (pin "29") (pinfunction "SD3/IO10_29") (pintype "unspecified"))
    )
    (net (code "70") (name "unconnected-(U4-SENSOR_CAPN{slash}I38-Pad7)") (class "Default")
      (node (ref "U4") (pin "7") (pinfunction "SENSOR_CAPN/I38_7") (pintype "unspecified"))
    )
    (net (code "71") (name "unconnected-(U4-SENSOR_CAPP{slash}I37-Pad6)") (class "Default")
      (node (ref "U4") (pin "6") (pinfunction "SENSOR_CAPP/I37_6") (pintype "unspecified"))
    )
    (net (code "72") (name "unconnected-(U4-SENSOR_VN{slash}I39-Pad8)") (class "Default")
      (node (ref "U4") (pin "8") (pinfunction "SENSOR_VN/I39_8") (pintype "unspecified"))
    )
    (net (code "73") (name "unconnected-(U4-SENSOR_VP{slash}I36-Pad5)") (class "Default")
      (node (ref "U4") (pin "5") (pinfunction "SENSOR_VP/I36_5") (pintype "unspecified"))
    )
    (net (code "74") (name "unconnected-(U4-VDET_1{slash}I34-Pad10)") (class "Default")
      (node (ref "U4") (pin "10") (pinfunction "VDET_1/I34_10") (pintype "unspecified"))
    )
    (net (code "75") (name "unconnected-(U4-VDET_2{slash}I35-Pad11)") (class "Default")
      (node (ref "U4") (pin "11") (pinfunction "VDET_2/I35_11") (pintype "unspecified"))
    )
    (net (code "76") (name "unconnected-(U5-GDO2-Pad3)") (class "Default")
      (node (ref "U5") (pin "3") (pinfunction "GDO2_3") (pintype "unspecified"))
    )
  )
)
